# riffle-CTD.net
KiCad netlist of a schematic drawn in EAGLE
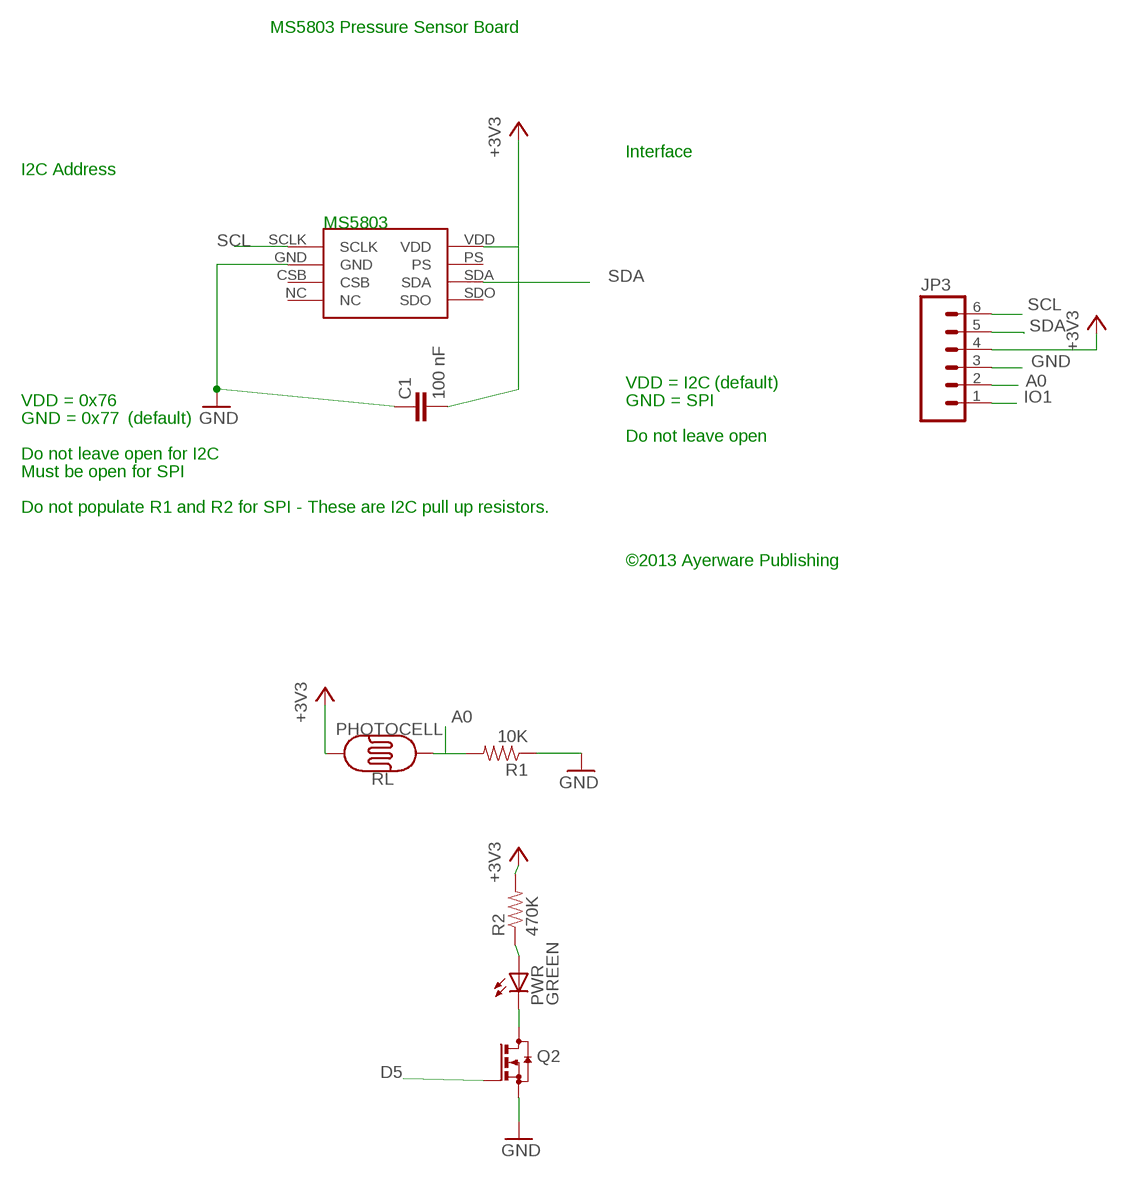
[diagram p0: schematic, sheet 1]

(export (version "E")
  (design (tool "Eeschema 10.0.6"))
  (components
    (comp (ref "C1")
      (value "100 nF")
      (footprint "eagle-import:0402-CAP")
      (libsource (lib "eagle-import") (part "CAP0402-CAP"))
    )
    (comp (ref "JP3")
      (value "M06SIP")
      (footprint "eagle-import:1X06")
      (libsource (lib "eagle-import") (part "M06SIP"))
    )
    (comp (ref "MS5803")
      (value "MS5803-14BA")
      (footprint "eagle-import:MS5803-14BA")
      (libsource (lib "eagle-import") (part "MS5803-14BA"))
    )
    (comp (ref "PWR")
      (value "GREEN")
      (footprint "eagle-import:CHIPLED_0805")
      (libsource (lib "eagle-import") (part "LEDCHIPLED_0805"))
    )
    (comp (ref "Q2")
      (value "BSS123")
      (footprint "eagle-import:SOT23")
      (libsource (lib "eagle-import") (part "BSS123"))
    )
    (comp (ref "R1")
      (value "10K")
      (footprint "eagle-import:0402-RES")
      (libsource (lib "eagle-import") (part "RESISTOR0402-RES"))
    )
    (comp (ref "R2")
      (value "470K")
      (footprint "eagle-import:0402-RES")
      (libsource (lib "eagle-import") (part "RESISTOR0402-RES"))
    )
    (comp (ref "RL")
      (value "PHOTOCELL")
      (footprint "eagle-import:PHOTOCELL")
      (libsource (lib "eagle-import") (part "PHOTOCELLPTH"))
    )
  )
  (nets
    (net (code "1") (name "+3V3") (class "Default")
      (node (ref "C1") (pin "1") (pinfunction "1_1") (pintype "passive"))
      (node (ref "JP3") (pin "4") (pinfunction "4_4") (pintype "passive"))
      (node (ref "MS5803") (pin "VDD") (pinfunction "VDD_VDD") (pintype "bidirectional"))
      (node (ref "R2") (pin "2") (pinfunction "2_2") (pintype "passive"))
      (node (ref "RL") (pin "2") (pinfunction "P$2_2") (pintype "bidirectional"))
    )
    (net (code "2") (name "/A0") (class "Default")
      (node (ref "JP3") (pin "2") (pinfunction "2_2") (pintype "passive"))
      (node (ref "R1") (pin "2") (pinfunction "2_2") (pintype "passive"))
      (node (ref "RL") (pin "1") (pinfunction "P$1_1") (pintype "bidirectional"))
    )
    (net (code "3") (name "/D5") (class "Default")
      (node (ref "Q2") (pin "1") (pinfunction "G_1") (pintype "passive"))
    )
    (net (code "4") (name "/IO1") (class "Default")
      (node (ref "JP3") (pin "1") (pinfunction "1_1") (pintype "passive"))
    )
    (net (code "5") (name "/SCL") (class "Default")
      (node (ref "JP3") (pin "6") (pinfunction "6_6") (pintype "passive"))
      (node (ref "MS5803") (pin "SCLK") (pinfunction "SCLK_SCLK") (pintype "bidirectional"))
    )
    (net (code "6") (name "/SDA") (class "Default")
      (node (ref "JP3") (pin "5") (pinfunction "5_5") (pintype "passive"))
      (node (ref "MS5803") (pin "SDA") (pinfunction "SDA_SDA") (pintype "bidirectional"))
    )
    (net (code "7") (name "GND") (class "Default")
      (node (ref "C1") (pin "2") (pinfunction "2_2") (pintype "passive"))
      (node (ref "JP3") (pin "3") (pinfunction "3_3") (pintype "passive"))
      (node (ref "MS5803") (pin "GND") (pinfunction "GND_GND") (pintype "bidirectional"))
      (node (ref "Q2") (pin "2") (pinfunction "S_2") (pintype "passive"))
      (node (ref "R1") (pin "1") (pinfunction "1_1") (pintype "passive"))
    )
    (net (code "8") (name "Net-(PWR-PadA)") (class "Default")
      (node (ref "PWR") (pin "A") (pinfunction "A_A") (pintype "passive"))
      (node (ref "R2") (pin "1") (pinfunction "1_1") (pintype "passive"))
    )
    (net (code "9") (name "Net-(Q2-D)") (class "Default")
      (node (ref "PWR") (pin "C") (pinfunction "C_C") (pintype "passive"))
      (node (ref "Q2") (pin "3") (pinfunction "D_3") (pintype "passive"))
    )
    (net (code "10") (name "unconnected-(MS5803-PadCSB)") (class "Default")
      (node (ref "MS5803") (pin "CSB") (pinfunction "CSB_CSB") (pintype "bidirectional"))
    )
    (net (code "11") (name "unconnected-(MS5803-PadNC)") (class "Default")
      (node (ref "MS5803") (pin "NC") (pinfunction "NC_NC") (pintype "bidirectional"))
    )
    (net (code "12") (name "unconnected-(MS5803-PadPS)") (class "Default")
      (node (ref "MS5803") (pin "PS") (pinfunction "PS_PS") (pintype "bidirectional"))
    )
    (net (code "13") (name "unconnected-(MS5803-PadSDO)") (class "Default")
      (node (ref "MS5803") (pin "SDO") (pinfunction "SDO_SDO") (pintype "bidirectional"))
    )
  )
)
